# encoder.net
KiCad netlist of a schematic drawn in EAGLE
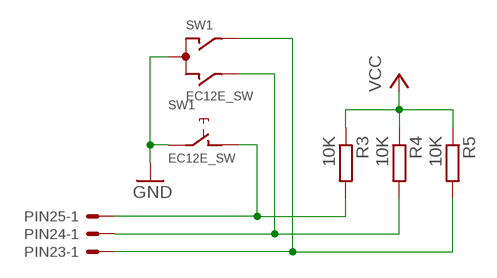
[diagram p0: schematic, sheet 1]

(export (version "E")
  (design (tool "Eeschema 10.0.6"))
  (components
    (comp (ref "PIN23")
      (value "5566-10")
      (footprint "eagle-import:5566-10")
      (libsource (lib "eagle-import") (part "5566-10"))
    )
    (comp (ref "PIN24")
      (value "5566-10")
      (footprint "eagle-import:5566-10")
      (libsource (lib "eagle-import") (part "5566-10"))
    )
    (comp (ref "PIN25")
      (value "5566-10")
      (footprint "eagle-import:5566-10")
      (libsource (lib "eagle-import") (part "5566-10"))
    )
    (comp (ref "R3")
      (value "10K")
      (footprint "eagle-import:M1206")
      (libsource (lib "eagle-import") (part "R-EU_M1206"))
    )
    (comp (ref "R4")
      (value "10K")
      (footprint "eagle-import:M1206")
      (libsource (lib "eagle-import") (part "R-EU_M1206"))
    )
    (comp (ref "R5")
      (value "10K")
      (footprint "eagle-import:M1206")
      (libsource (lib "eagle-import") (part "R-EU_M1206"))
    )
    (comp (ref "SW1")
      (value "EC12E_SW")
      (footprint "eagle-import:ALPS_EC12E_SW")
      (fields (field (name "MPN") "EC12E2424407"))
      (libsource (lib "eagle-import") (part "EC12E_SW"))
    )
  )
  (nets
    (net (code "1") (name "GND") (class "Default")
      (node (ref "SW1") (pin "C") (pinfunction "C_C") (pintype "passive"))
      (node (ref "SW1") (pin "E") (pinfunction "2_E") (pintype "passive"))
    )
    (net (code "2") (name "Net-(PIN23A-S)") (class "Default")
      (node (ref "PIN23") (pin "1") (pinfunction "S_1") (pintype "passive"))
      (node (ref "R5") (pin "2") (pinfunction "2_2") (pintype "passive"))
      (node (ref "SW1") (pin "A") (pinfunction "A_A") (pintype "passive"))
    )
    (net (code "3") (name "Net-(PIN24A-S)") (class "Default")
      (node (ref "PIN24") (pin "1") (pinfunction "S_1") (pintype "passive"))
      (node (ref "R4") (pin "2") (pinfunction "2_2") (pintype "passive"))
      (node (ref "SW1") (pin "B") (pinfunction "B_B") (pintype "passive"))
    )
    (net (code "4") (name "Net-(PIN25A-S)") (class "Default")
      (node (ref "PIN25") (pin "1") (pinfunction "S_1") (pintype "passive"))
      (node (ref "R3") (pin "2") (pinfunction "2_2") (pintype "passive"))
      (node (ref "SW1") (pin "D") (pinfunction "1_D") (pintype "passive"))
    )
    (net (code "5") (name "VCC") (class "Default")
      (node (ref "R3") (pin "1") (pinfunction "1_1") (pintype "passive"))
      (node (ref "R4") (pin "1") (pinfunction "1_1") (pintype "passive"))
      (node (ref "R5") (pin "1") (pinfunction "1_1") (pintype "passive"))
    )
  )
)
